# elec.net
KiCad netlist of a schematic drawn in Altium Designer
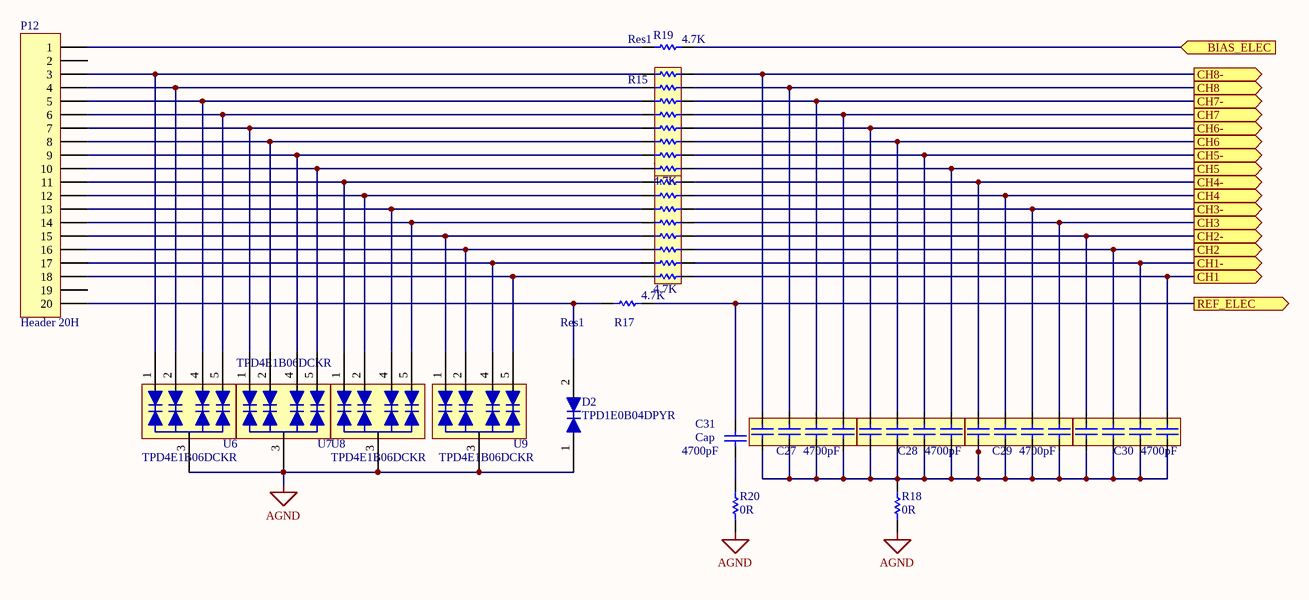
[diagram p0: elec.SchDoc]

(export (version "E")
  (design (tool "Eeschema 10.0.6"))
  (components
    (comp (ref "C27")
      (value "50V")
      (footprint "1206C-ARRAY")
      (description "CAP .1UF 50V CERAMIC Y5V 0805")
      (fields
        (field (name "MANUFACTURER") "TDK")
        (field (name "PCN PART NUMBER") "MLCC Part Number Change 30/Nov/2012")
        (field (name "CAPACITANCE") "4700pF")
      )
      (libsource (lib "LUCHADOR SCHLIB") (part "Cap"))
    )
    (comp (ref "C28")
      (value "50V")
      (footprint "1206C-ARRAY")
      (description "CAP .1UF 50V CERAMIC Y5V 0805")
      (fields
        (field (name "MANUFACTURER") "TDK")
        (field (name "PCN PART NUMBER") "MLCC Part Number Change 30/Nov/2012")
        (field (name "CAPACITANCE") "4700pF")
      )
      (libsource (lib "LUCHADOR SCHLIB") (part "Cap"))
    )
    (comp (ref "C29")
      (value "50V")
      (footprint "1206C-ARRAY")
      (description "CAP .1UF 50V CERAMIC Y5V 0805")
      (fields
        (field (name "MANUFACTURER") "TDK")
        (field (name "PCN PART NUMBER") "MLCC Part Number Change 30/Nov/2012")
        (field (name "CAPACITANCE") "4700pF")
      )
      (libsource (lib "LUCHADOR SCHLIB") (part "Cap"))
    )
    (comp (ref "C30")
      (value "50V")
      (footprint "1206C-ARRAY")
      (description "CAP .1UF 50V CERAMIC Y5V 0805")
      (fields
        (field (name "MANUFACTURER") "TDK")
        (field (name "PCN PART NUMBER") "MLCC Part Number Change 30/Nov/2012")
        (field (name "CAPACITANCE") "4700pF")
      )
      (libsource (lib "LUCHADOR SCHLIB") (part "Cap"))
    )
    (comp (ref "C31")
      (value "Cap")
      (footprint "0402C")
      (description "Capacitor")
      (fields (field (name "ALTIUM_VALUE") "4700pF") (field (name "PUBLISHER") "Altium Limited"))
      (libsource (lib "Miscellaneous Devices") (part "Cap"))
    )
    (comp (ref "D2")
      (value "TPD1E0B04DPYR")
      (footprint "0402D")
      (fields
        (field (name "MANUFACTURER") "Texas Instruments")
        (field (name "MANUFACTURER PART NUMBER") "TPD1E0B04DPYR")
      )
      (libsource (lib "LUCHADOR SCHLIB") (part "TPD1E0B04DPYR"))
    )
    (comp (ref "P12")
      (value "Header 20H")
      (footprint "HDR1X20H")
      (description "Header, 20-Pin, Right Angle")
      (fields (field (name "PUBLISHER") "Altium Limited"))
      (libsource (lib "Miscellaneous Connectors") (part "Header 20H"))
    )
    (comp (ref "R15")
      (value "RES 8X")
      (footprint "1506R")
      (description "Resistor")
      (fields
        (field (name "MANUFACTURER") "Panasonic")
        (field (name "MANUFACTURER PART NUMBER") "EXB-2HV472JV")
        (field (name "RESISTANCE") "4.7K")
      )
      (libsource (lib "LUCHADOR SCHLIB") (part "RES 8X"))
    )
    (comp (ref "R16")
      (value "RES 8X")
      (footprint "1506R")
      (description "Resistor")
      (fields
        (field (name "MANUFACTURER") "Panasonic")
        (field (name "MANUFACTURER PART NUMBER") "EXB-2HV472JV")
        (field (name "RESISTANCE") "4.7K")
      )
      (libsource (lib "LUCHADOR SCHLIB") (part "RES 8X"))
    )
    (comp (ref "R17")
      (value "Res1")
      (footprint "0603")
      (description "Resistor")
      (fields (field (name "ALTIUM_VALUE") "4.7K") (field (name "PUBLISHER") "Altium Limited"))
      (libsource (lib "Miscellaneous Devices") (part "Res1"))
    )
    (comp (ref "R18")
      (value "Res 0805")
      (footprint "0603")
      (description "Resistor")
      (fields
        (field (name "MANUFACTURER") "Panasonic")
        (field (name "MANUFACTURER PART NUMBER") "ERJ-2GE0R00X")
        (field (name "RESISTANCE (OHMS)") "0R")
      )
      (libsource (lib "RAPTOR MCB SCHLIB") (part "Res 0805"))
    )
    (comp (ref "R19")
      (value "Res1")
      (footprint "0603")
      (description "Resistor")
      (fields (field (name "ALTIUM_VALUE") "4.7K") (field (name "PUBLISHER") "Altium Limited"))
      (libsource (lib "Miscellaneous Devices") (part "Res1"))
    )
    (comp (ref "R20")
      (value "Res 0805")
      (footprint "0603")
      (description "Resistor")
      (fields
        (field (name "MANUFACTURER") "Panasonic")
        (field (name "MANUFACTURER PART NUMBER") "ERJ-2GE0R00X")
        (field (name "RESISTANCE (OHMS)") "0R")
      )
      (libsource (lib "RAPTOR MCB SCHLIB") (part "Res 0805"))
    )
    (comp (ref "U6")
      (value "TPD4E1B06DCKR")
      (footprint "DCK6_TEX")
      (fields
        (field (name "MANUFACTURER") "Texas Instruments")
        (field (name "MANUFACTURER PART NUMBER") "TPD4E1B06DCKR")
      )
      (libsource (lib "LUCHADOR SCHLIB") (part "TPD4E1B06DCKR"))
    )
    (comp (ref "U7")
      (value "TPD4E1B06DCKR")
      (footprint "DCK6_TEX")
      (fields
        (field (name "MANUFACTURER") "Texas Instruments")
        (field (name "MANUFACTURER PART NUMBER") "TPD4E1B06DCKR")
      )
      (libsource (lib "LUCHADOR SCHLIB") (part "TPD4E1B06DCKR"))
    )
    (comp (ref "U8")
      (value "TPD4E1B06DCKR")
      (footprint "DCK6_TEX")
      (fields
        (field (name "MANUFACTURER") "Texas Instruments")
        (field (name "MANUFACTURER PART NUMBER") "TPD4E1B06DCKR")
      )
      (libsource (lib "LUCHADOR SCHLIB") (part "TPD4E1B06DCKR"))
    )
    (comp (ref "U9")
      (value "TPD4E1B06DCKR")
      (footprint "DCK6_TEX")
      (fields
        (field (name "MANUFACTURER") "Texas Instruments")
        (field (name "MANUFACTURER PART NUMBER") "TPD4E1B06DCKR")
      )
      (libsource (lib "LUCHADOR SCHLIB") (part "TPD4E1B06DCKR"))
    )
  )
  (nets
    (net (code "1") (name "/BIAS_ELEC") (class "Default")
      (node (ref "R19") (pin "2") (pinfunction "2_2") (pintype "passive"))
    )
    (net (code "2") (name "/CH1") (class "Default")
      (node (ref "C30") (pin "A4") (pinfunction "A4_A4") (pintype "passive"))
      (node (ref "R16") (pin "B8") (pinfunction "B8_B8") (pintype "passive"))
    )
    (net (code "3") (name "/CH1-") (class "Default")
      (node (ref "C30") (pin "A3") (pinfunction "A3_A3") (pintype "passive"))
      (node (ref "R16") (pin "B7") (pinfunction "B7_B7") (pintype "passive"))
    )
    (net (code "4") (name "/CH2") (class "Default")
      (node (ref "C30") (pin "A2") (pinfunction "A2_A2") (pintype "passive"))
      (node (ref "R16") (pin "B6") (pinfunction "B6_B6") (pintype "passive"))
    )
    (net (code "5") (name "/CH2-") (class "Default")
      (node (ref "C30") (pin "A1") (pinfunction "A1_A1") (pintype "passive"))
      (node (ref "R16") (pin "B5") (pinfunction "B5_B5") (pintype "passive"))
    )
    (net (code "6") (name "/CH3") (class "Default")
      (node (ref "C29") (pin "A4") (pinfunction "A4_A4") (pintype "passive"))
      (node (ref "R16") (pin "B4") (pinfunction "B4_B4") (pintype "passive"))
    )
    (net (code "7") (name "/CH3-") (class "Default")
      (node (ref "C29") (pin "A3") (pinfunction "A3_A3") (pintype "passive"))
      (node (ref "R16") (pin "B3") (pinfunction "B3_B3") (pintype "passive"))
    )
    (net (code "8") (name "/CH4") (class "Default")
      (node (ref "C29") (pin "A2") (pinfunction "A2_A2") (pintype "passive"))
      (node (ref "R16") (pin "B2") (pinfunction "B2_B2") (pintype "passive"))
    )
    (net (code "9") (name "/CH4-") (class "Default")
      (node (ref "C29") (pin "A1") (pinfunction "A1_A1") (pintype "passive"))
      (node (ref "R16") (pin "B1") (pinfunction "B1_B1") (pintype "passive"))
    )
    (net (code "10") (name "/CH5") (class "Default")
      (node (ref "C28") (pin "A4") (pinfunction "A4_A4") (pintype "passive"))
      (node (ref "R15") (pin "B8") (pinfunction "B8_B8") (pintype "passive"))
    )
    (net (code "11") (name "/CH5-") (class "Default")
      (node (ref "C28") (pin "A3") (pinfunction "A3_A3") (pintype "passive"))
      (node (ref "R15") (pin "B7") (pinfunction "B7_B7") (pintype "passive"))
    )
    (net (code "12") (name "/CH6") (class "Default")
      (node (ref "C28") (pin "A2") (pinfunction "A2_A2") (pintype "passive"))
      (node (ref "R15") (pin "B6") (pinfunction "B6_B6") (pintype "passive"))
    )
    (net (code "13") (name "/CH6-") (class "Default")
      (node (ref "C28") (pin "A1") (pinfunction "A1_A1") (pintype "passive"))
      (node (ref "R15") (pin "B5") (pinfunction "B5_B5") (pintype "passive"))
    )
    (net (code "14") (name "/CH7") (class "Default")
      (node (ref "C27") (pin "A4") (pinfunction "A4_A4") (pintype "passive"))
      (node (ref "R15") (pin "B4") (pinfunction "B4_B4") (pintype "passive"))
    )
    (net (code "15") (name "/CH7-") (class "Default")
      (node (ref "C27") (pin "A3") (pinfunction "A3_A3") (pintype "passive"))
      (node (ref "R15") (pin "B3") (pinfunction "B3_B3") (pintype "passive"))
    )
    (net (code "16") (name "/CH8") (class "Default")
      (node (ref "C27") (pin "A2") (pinfunction "A2_A2") (pintype "passive"))
      (node (ref "R15") (pin "B2") (pinfunction "B2_B2") (pintype "passive"))
    )
    (net (code "17") (name "/CH8-") (class "Default")
      (node (ref "C27") (pin "A1") (pinfunction "A1_A1") (pintype "passive"))
      (node (ref "R15") (pin "B1") (pinfunction "B1_B1") (pintype "passive"))
    )
    (net (code "18") (name "/REF_ELEC") (class "Default")
      (node (ref "C31") (pin "2") (pinfunction "2_2") (pintype "passive"))
      (node (ref "R17") (pin "2") (pinfunction "2_2") (pintype "passive"))
    )
    (net (code "19") (name "AGND") (class "Default")
      (node (ref "D2") (pin "1") (pinfunction "IO1_1") (pintype "passive"))
      (node (ref "R18") (pin "1") (pinfunction "1_1") (pintype "passive"))
      (node (ref "R20") (pin "1") (pinfunction "1_1") (pintype "passive"))
      (node (ref "U6") (pin "3") (pinfunction "GND_3") (pintype "passive"))
      (node (ref "U7") (pin "3") (pinfunction "GND_3") (pintype "passive"))
      (node (ref "U8") (pin "3") (pinfunction "GND_3") (pintype "passive"))
      (node (ref "U9") (pin "3") (pinfunction "GND_3") (pintype "passive"))
    )
    (net (code "20") (name "Net-(C27-PadB1)") (class "Default")
      (node (ref "C27") (pin "B1") (pinfunction "B1_B1") (pintype "passive"))
      (node (ref "C27") (pin "B2") (pinfunction "B2_B2") (pintype "passive"))
      (node (ref "C27") (pin "B3") (pinfunction "B3_B3") (pintype "passive"))
      (node (ref "C27") (pin "B4") (pinfunction "B4_B4") (pintype "passive"))
      (node (ref "C28") (pin "B1") (pinfunction "B1_B1") (pintype "passive"))
      (node (ref "C28") (pin "B2") (pinfunction "B2_B2") (pintype "passive"))
      (node (ref "C28") (pin "B3") (pinfunction "B3_B3") (pintype "passive"))
      (node (ref "C28") (pin "B4") (pinfunction "B4_B4") (pintype "passive"))
      (node (ref "C29") (pin "B1") (pinfunction "B1_B1") (pintype "passive"))
      (node (ref "C29") (pin "B2") (pinfunction "B2_B2") (pintype "passive"))
      (node (ref "C29") (pin "B3") (pinfunction "B3_B3") (pintype "passive"))
      (node (ref "C29") (pin "B4") (pinfunction "B4_B4") (pintype "passive"))
      (node (ref "C30") (pin "B1") (pinfunction "B1_B1") (pintype "passive"))
      (node (ref "C30") (pin "B2") (pinfunction "B2_B2") (pintype "passive"))
      (node (ref "C30") (pin "B3") (pinfunction "B3_B3") (pintype "passive"))
      (node (ref "C30") (pin "B4") (pinfunction "B4_B4") (pintype "passive"))
      (node (ref "R18") (pin "2") (pinfunction "2_2") (pintype "passive"))
    )
    (net (code "21") (name "Net-(C31-Pad1)") (class "Default")
      (node (ref "C31") (pin "1") (pinfunction "1_1") (pintype "passive"))
      (node (ref "R20") (pin "2") (pinfunction "2_2") (pintype "passive"))
    )
    (net (code "22") (name "Net-(D2-GND)") (class "Default")
      (node (ref "D2") (pin "2") (pinfunction "GND_2") (pintype "passive"))
      (node (ref "P12") (pin "20") (pinfunction "20_20") (pintype "passive"))
      (node (ref "R17") (pin "1") (pinfunction "1_1") (pintype "passive"))
    )
    (net (code "23") (name "Net-(P12-Pad1)") (class "Default")
      (node (ref "P12") (pin "1") (pinfunction "1_1") (pintype "passive"))
      (node (ref "R19") (pin "1") (pinfunction "1_1") (pintype "passive"))
    )
    (net (code "24") (name "Net-(U6-IO1)") (class "Default")
      (node (ref "P12") (pin "3") (pinfunction "3_3") (pintype "passive"))
      (node (ref "R15") (pin "A1") (pinfunction "A1_A1") (pintype "passive"))
      (node (ref "U6") (pin "1") (pinfunction "IO1_1") (pintype "passive"))
    )
    (net (code "25") (name "Net-(U6-IO2)") (class "Default")
      (node (ref "P12") (pin "4") (pinfunction "4_4") (pintype "passive"))
      (node (ref "R15") (pin "A2") (pinfunction "A2_A2") (pintype "passive"))
      (node (ref "U6") (pin "2") (pinfunction "IO2_2") (pintype "passive"))
    )
    (net (code "26") (name "Net-(U6-IO3)") (class "Default")
      (node (ref "P12") (pin "5") (pinfunction "5_5") (pintype "passive"))
      (node (ref "R15") (pin "A3") (pinfunction "A3_A3") (pintype "passive"))
      (node (ref "U6") (pin "4") (pinfunction "IO3_4") (pintype "passive"))
    )
    (net (code "27") (name "Net-(U6-IO4)") (class "Default")
      (node (ref "P12") (pin "6") (pinfunction "6_6") (pintype "passive"))
      (node (ref "R15") (pin "A4") (pinfunction "A4_A4") (pintype "passive"))
      (node (ref "U6") (pin "5") (pinfunction "IO4_5") (pintype "passive"))
    )
    (net (code "28") (name "Net-(U7-IO1)") (class "Default")
      (node (ref "P12") (pin "7") (pinfunction "7_7") (pintype "passive"))
      (node (ref "R15") (pin "A5") (pinfunction "A5_A5") (pintype "passive"))
      (node (ref "U7") (pin "1") (pinfunction "IO1_1") (pintype "passive"))
    )
    (net (code "29") (name "Net-(U7-IO2)") (class "Default")
      (node (ref "P12") (pin "8") (pinfunction "8_8") (pintype "passive"))
      (node (ref "R15") (pin "A6") (pinfunction "A6_A6") (pintype "passive"))
      (node (ref "U7") (pin "2") (pinfunction "IO2_2") (pintype "passive"))
    )
    (net (code "30") (name "Net-(U7-IO3)") (class "Default")
      (node (ref "P12") (pin "9") (pinfunction "9_9") (pintype "passive"))
      (node (ref "R15") (pin "A7") (pinfunction "A7_A7") (pintype "passive"))
      (node (ref "U7") (pin "4") (pinfunction "IO3_4") (pintype "passive"))
    )
    (net (code "31") (name "Net-(U7-IO4)") (class "Default")
      (node (ref "P12") (pin "10") (pinfunction "10_10") (pintype "passive"))
      (node (ref "R15") (pin "A8") (pinfunction "A8_A8") (pintype "passive"))
      (node (ref "U7") (pin "5") (pinfunction "IO4_5") (pintype "passive"))
    )
    (net (code "32") (name "Net-(U8-IO1)") (class "Default")
      (node (ref "P12") (pin "11") (pinfunction "11_11") (pintype "passive"))
      (node (ref "R16") (pin "A1") (pinfunction "A1_A1") (pintype "passive"))
      (node (ref "U8") (pin "1") (pinfunction "IO1_1") (pintype "passive"))
    )
    (net (code "33") (name "Net-(U8-IO2)") (class "Default")
      (node (ref "P12") (pin "12") (pinfunction "12_12") (pintype "passive"))
      (node (ref "R16") (pin "A2") (pinfunction "A2_A2") (pintype "passive"))
      (node (ref "U8") (pin "2") (pinfunction "IO2_2") (pintype "passive"))
    )
    (net (code "34") (name "Net-(U8-IO3)") (class "Default")
      (node (ref "P12") (pin "13") (pinfunction "13_13") (pintype "passive"))
      (node (ref "R16") (pin "A3") (pinfunction "A3_A3") (pintype "passive"))
      (node (ref "U8") (pin "4") (pinfunction "IO3_4") (pintype "passive"))
    )
    (net (code "35") (name "Net-(U8-IO4)") (class "Default")
      (node (ref "P12") (pin "14") (pinfunction "14_14") (pintype "passive"))
      (node (ref "R16") (pin "A4") (pinfunction "A4_A4") (pintype "passive"))
      (node (ref "U8") (pin "5") (pinfunction "IO4_5") (pintype "passive"))
    )
    (net (code "36") (name "Net-(U9-IO1)") (class "Default")
      (node (ref "P12") (pin "15") (pinfunction "15_15") (pintype "passive"))
      (node (ref "R16") (pin "A5") (pinfunction "A5_A5") (pintype "passive"))
      (node (ref "U9") (pin "1") (pinfunction "IO1_1") (pintype "passive"))
    )
    (net (code "37") (name "Net-(U9-IO2)") (class "Default")
      (node (ref "P12") (pin "16") (pinfunction "16_16") (pintype "passive"))
      (node (ref "R16") (pin "A6") (pinfunction "A6_A6") (pintype "passive"))
      (node (ref "U9") (pin "2") (pinfunction "IO2_2") (pintype "passive"))
    )
    (net (code "38") (name "Net-(U9-IO3)") (class "Default")
      (node (ref "P12") (pin "17") (pinfunction "17_17") (pintype "passive"))
      (node (ref "R16") (pin "A7") (pinfunction "A7_A7") (pintype "passive"))
      (node (ref "U9") (pin "4") (pinfunction "IO3_4") (pintype "passive"))
    )
    (net (code "39") (name "Net-(U9-IO4)") (class "Default")
      (node (ref "P12") (pin "18") (pinfunction "18_18") (pintype "passive"))
      (node (ref "R16") (pin "A8") (pinfunction "A8_A8") (pintype "passive"))
      (node (ref "U9") (pin "5") (pinfunction "IO4_5") (pintype "passive"))
    )
    (net (code "40") (name "unconnected-(P12-Pad2)") (class "Default")
      (node (ref "P12") (pin "2") (pinfunction "2_2") (pintype "passive"))
    )
    (net (code "41") (name "unconnected-(P12-Pad19)") (class "Default")
      (node (ref "P12") (pin "19") (pinfunction "19_19") (pintype "passive"))
    )
  )
)
